# 360-wearable.net
KiCad netlist of a schematic drawn in EAGLE
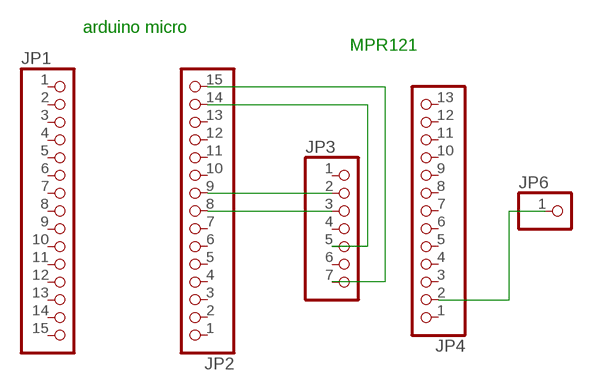
[diagram p0: schematic, sheet 1]

(export (version "E")
  (design (tool "Eeschema 10.0.6"))
  (components
    (comp (ref "JP1")
      (value "PINHD-1X15")
      (footprint "eagle-import:1X15")
      (libsource (lib "eagle-import") (part "PINHD-1X15"))
    )
    (comp (ref "JP2")
      (value "PINHD-1X15")
      (footprint "eagle-import:1X15")
      (libsource (lib "eagle-import") (part "PINHD-1X15"))
    )
    (comp (ref "JP3")
      (value "PINHD-1X7")
      (footprint "eagle-import:1X07")
      (libsource (lib "eagle-import") (part "PINHD-1X7"))
    )
    (comp (ref "JP4")
      (value "PINHD-1X13")
      (footprint "eagle-import:1X13")
      (libsource (lib "eagle-import") (part "PINHD-1X13"))
    )
    (comp (ref "JP6")
      (value "PINHD-1X1")
      (footprint "eagle-import:1X01")
      (libsource (lib "eagle-import") (part "PINHD-1X1"))
    )
  )
  (nets
    (net (code "1") (name "Net-(JP2-Pad8)") (class "Default")
      (node (ref "JP2") (pin "8") (pinfunction "8_8") (pintype "passive"))
      (node (ref "JP3") (pin "3") (pinfunction "3_3") (pintype "passive"))
    )
    (net (code "2") (name "Net-(JP2-Pad9)") (class "Default")
      (node (ref "JP2") (pin "9") (pinfunction "9_9") (pintype "passive"))
      (node (ref "JP3") (pin "2") (pinfunction "2_2") (pintype "passive"))
    )
    (net (code "3") (name "Net-(JP2-Pad14)") (class "Default")
      (node (ref "JP2") (pin "14") (pinfunction "14_14") (pintype "passive"))
      (node (ref "JP3") (pin "5") (pinfunction "5_5") (pintype "passive"))
    )
    (net (code "4") (name "Net-(JP2-Pad15)") (class "Default")
      (node (ref "JP2") (pin "15") (pinfunction "15_15") (pintype "passive"))
      (node (ref "JP3") (pin "7") (pinfunction "7_7") (pintype "passive"))
    )
    (net (code "5") (name "Net-(JP4-Pad2)") (class "Default")
      (node (ref "JP4") (pin "2") (pinfunction "2_2") (pintype "passive"))
      (node (ref "JP6") (pin "1") (pinfunction "1_1") (pintype "passive"))
    )
    (net (code "6") (name "unconnected-(JP1-Pad1)") (class "Default")
      (node (ref "JP1") (pin "1") (pinfunction "1_1") (pintype "passive"))
    )
    (net (code "7") (name "unconnected-(JP1-Pad2)") (class "Default")
      (node (ref "JP1") (pin "2") (pinfunction "2_2") (pintype "passive"))
    )
    (net (code "8") (name "unconnected-(JP1-Pad3)") (class "Default")
      (node (ref "JP1") (pin "3") (pinfunction "3_3") (pintype "passive"))
    )
    (net (code "9") (name "unconnected-(JP1-Pad4)") (class "Default")
      (node (ref "JP1") (pin "4") (pinfunction "4_4") (pintype "passive"))
    )
    (net (code "10") (name "unconnected-(JP1-Pad5)") (class "Default")
      (node (ref "JP1") (pin "5") (pinfunction "5_5") (pintype "passive"))
    )
    (net (code "11") (name "unconnected-(JP1-Pad6)") (class "Default")
      (node (ref "JP1") (pin "6") (pinfunction "6_6") (pintype "passive"))
    )
    (net (code "12") (name "unconnected-(JP1-Pad7)") (class "Default")
      (node (ref "JP1") (pin "7") (pinfunction "7_7") (pintype "passive"))
    )
    (net (code "13") (name "unconnected-(JP1-Pad8)") (class "Default")
      (node (ref "JP1") (pin "8") (pinfunction "8_8") (pintype "passive"))
    )
    (net (code "14") (name "unconnected-(JP1-Pad9)") (class "Default")
      (node (ref "JP1") (pin "9") (pinfunction "9_9") (pintype "passive"))
    )
    (net (code "15") (name "unconnected-(JP1-Pad10)") (class "Default")
      (node (ref "JP1") (pin "10") (pinfunction "10_10") (pintype "passive"))
    )
    (net (code "16") (name "unconnected-(JP1-Pad11)") (class "Default")
      (node (ref "JP1") (pin "11") (pinfunction "11_11") (pintype "passive"))
    )
    (net (code "17") (name "unconnected-(JP1-Pad12)") (class "Default")
      (node (ref "JP1") (pin "12") (pinfunction "12_12") (pintype "passive"))
    )
    (net (code "18") (name "unconnected-(JP1-Pad13)") (class "Default")
      (node (ref "JP1") (pin "13") (pinfunction "13_13") (pintype "passive"))
    )
    (net (code "19") (name "unconnected-(JP1-Pad14)") (class "Default")
      (node (ref "JP1") (pin "14") (pinfunction "14_14") (pintype "passive"))
    )
    (net (code "20") (name "unconnected-(JP1-Pad15)") (class "Default")
      (node (ref "JP1") (pin "15") (pinfunction "15_15") (pintype "passive"))
    )
    (net (code "21") (name "unconnected-(JP2-Pad1)") (class "Default")
      (node (ref "JP2") (pin "1") (pinfunction "1_1") (pintype "passive"))
    )
    (net (code "22") (name "unconnected-(JP2-Pad2)") (class "Default")
      (node (ref "JP2") (pin "2") (pinfunction "2_2") (pintype "passive"))
    )
    (net (code "23") (name "unconnected-(JP2-Pad3)") (class "Default")
      (node (ref "JP2") (pin "3") (pinfunction "3_3") (pintype "passive"))
    )
    (net (code "24") (name "unconnected-(JP2-Pad4)") (class "Default")
      (node (ref "JP2") (pin "4") (pinfunction "4_4") (pintype "passive"))
    )
    (net (code "25") (name "unconnected-(JP2-Pad5)") (class "Default")
      (node (ref "JP2") (pin "5") (pinfunction "5_5") (pintype "passive"))
    )
    (net (code "26") (name "unconnected-(JP2-Pad6)") (class "Default")
      (node (ref "JP2") (pin "6") (pinfunction "6_6") (pintype "passive"))
    )
    (net (code "27") (name "unconnected-(JP2-Pad7)") (class "Default")
      (node (ref "JP2") (pin "7") (pinfunction "7_7") (pintype "passive"))
    )
    (net (code "28") (name "unconnected-(JP2-Pad10)") (class "Default")
      (node (ref "JP2") (pin "10") (pinfunction "10_10") (pintype "passive"))
    )
    (net (code "29") (name "unconnected-(JP2-Pad11)") (class "Default")
      (node (ref "JP2") (pin "11") (pinfunction "11_11") (pintype "passive"))
    )
    (net (code "30") (name "unconnected-(JP2-Pad12)") (class "Default")
      (node (ref "JP2") (pin "12") (pinfunction "12_12") (pintype "passive"))
    )
    (net (code "31") (name "unconnected-(JP2-Pad13)") (class "Default")
      (node (ref "JP2") (pin "13") (pinfunction "13_13") (pintype "passive"))
    )
    (net (code "32") (name "unconnected-(JP3-Pad1)") (class "Default")
      (node (ref "JP3") (pin "1") (pinfunction "1_1") (pintype "passive"))
    )
    (net (code "33") (name "unconnected-(JP3-Pad4)") (class "Default")
      (node (ref "JP3") (pin "4") (pinfunction "4_4") (pintype "passive"))
    )
    (net (code "34") (name "unconnected-(JP3-Pad6)") (class "Default")
      (node (ref "JP3") (pin "6") (pinfunction "6_6") (pintype "passive"))
    )
    (net (code "35") (name "unconnected-(JP4-Pad1)") (class "Default")
      (node (ref "JP4") (pin "1") (pinfunction "1_1") (pintype "passive"))
    )
    (net (code "36") (name "unconnected-(JP4-Pad3)") (class "Default")
      (node (ref "JP4") (pin "3") (pinfunction "3_3") (pintype "passive"))
    )
    (net (code "37") (name "unconnected-(JP4-Pad4)") (class "Default")
      (node (ref "JP4") (pin "4") (pinfunction "4_4") (pintype "passive"))
    )
    (net (code "38") (name "unconnected-(JP4-Pad5)") (class "Default")
      (node (ref "JP4") (pin "5") (pinfunction "5_5") (pintype "passive"))
    )
    (net (code "39") (name "unconnected-(JP4-Pad6)") (class "Default")
      (node (ref "JP4") (pin "6") (pinfunction "6_6") (pintype "passive"))
    )
    (net (code "40") (name "unconnected-(JP4-Pad7)") (class "Default")
      (node (ref "JP4") (pin "7") (pinfunction "7_7") (pintype "passive"))
    )
    (net (code "41") (name "unconnected-(JP4-Pad8)") (class "Default")
      (node (ref "JP4") (pin "8") (pinfunction "8_8") (pintype "passive"))
    )
    (net (code "42") (name "unconnected-(JP4-Pad9)") (class "Default")
      (node (ref "JP4") (pin "9") (pinfunction "9_9") (pintype "passive"))
    )
    (net (code "43") (name "unconnected-(JP4-Pad10)") (class "Default")
      (node (ref "JP4") (pin "10") (pinfunction "10_10") (pintype "passive"))
    )
    (net (code "44") (name "unconnected-(JP4-Pad11)") (class "Default")
      (node (ref "JP4") (pin "11") (pinfunction "11_11") (pintype "passive"))
    )
    (net (code "45") (name "unconnected-(JP4-Pad12)") (class "Default")
      (node (ref "JP4") (pin "12") (pinfunction "12_12") (pintype "passive"))
    )
    (net (code "46") (name "unconnected-(JP4-Pad13)") (class "Default")
      (node (ref "JP4") (pin "13") (pinfunction "13_13") (pintype "passive"))
    )
  )
)
